# PressureSensorAdaptor.net
KiCad netlist of a schematic drawn in EAGLE
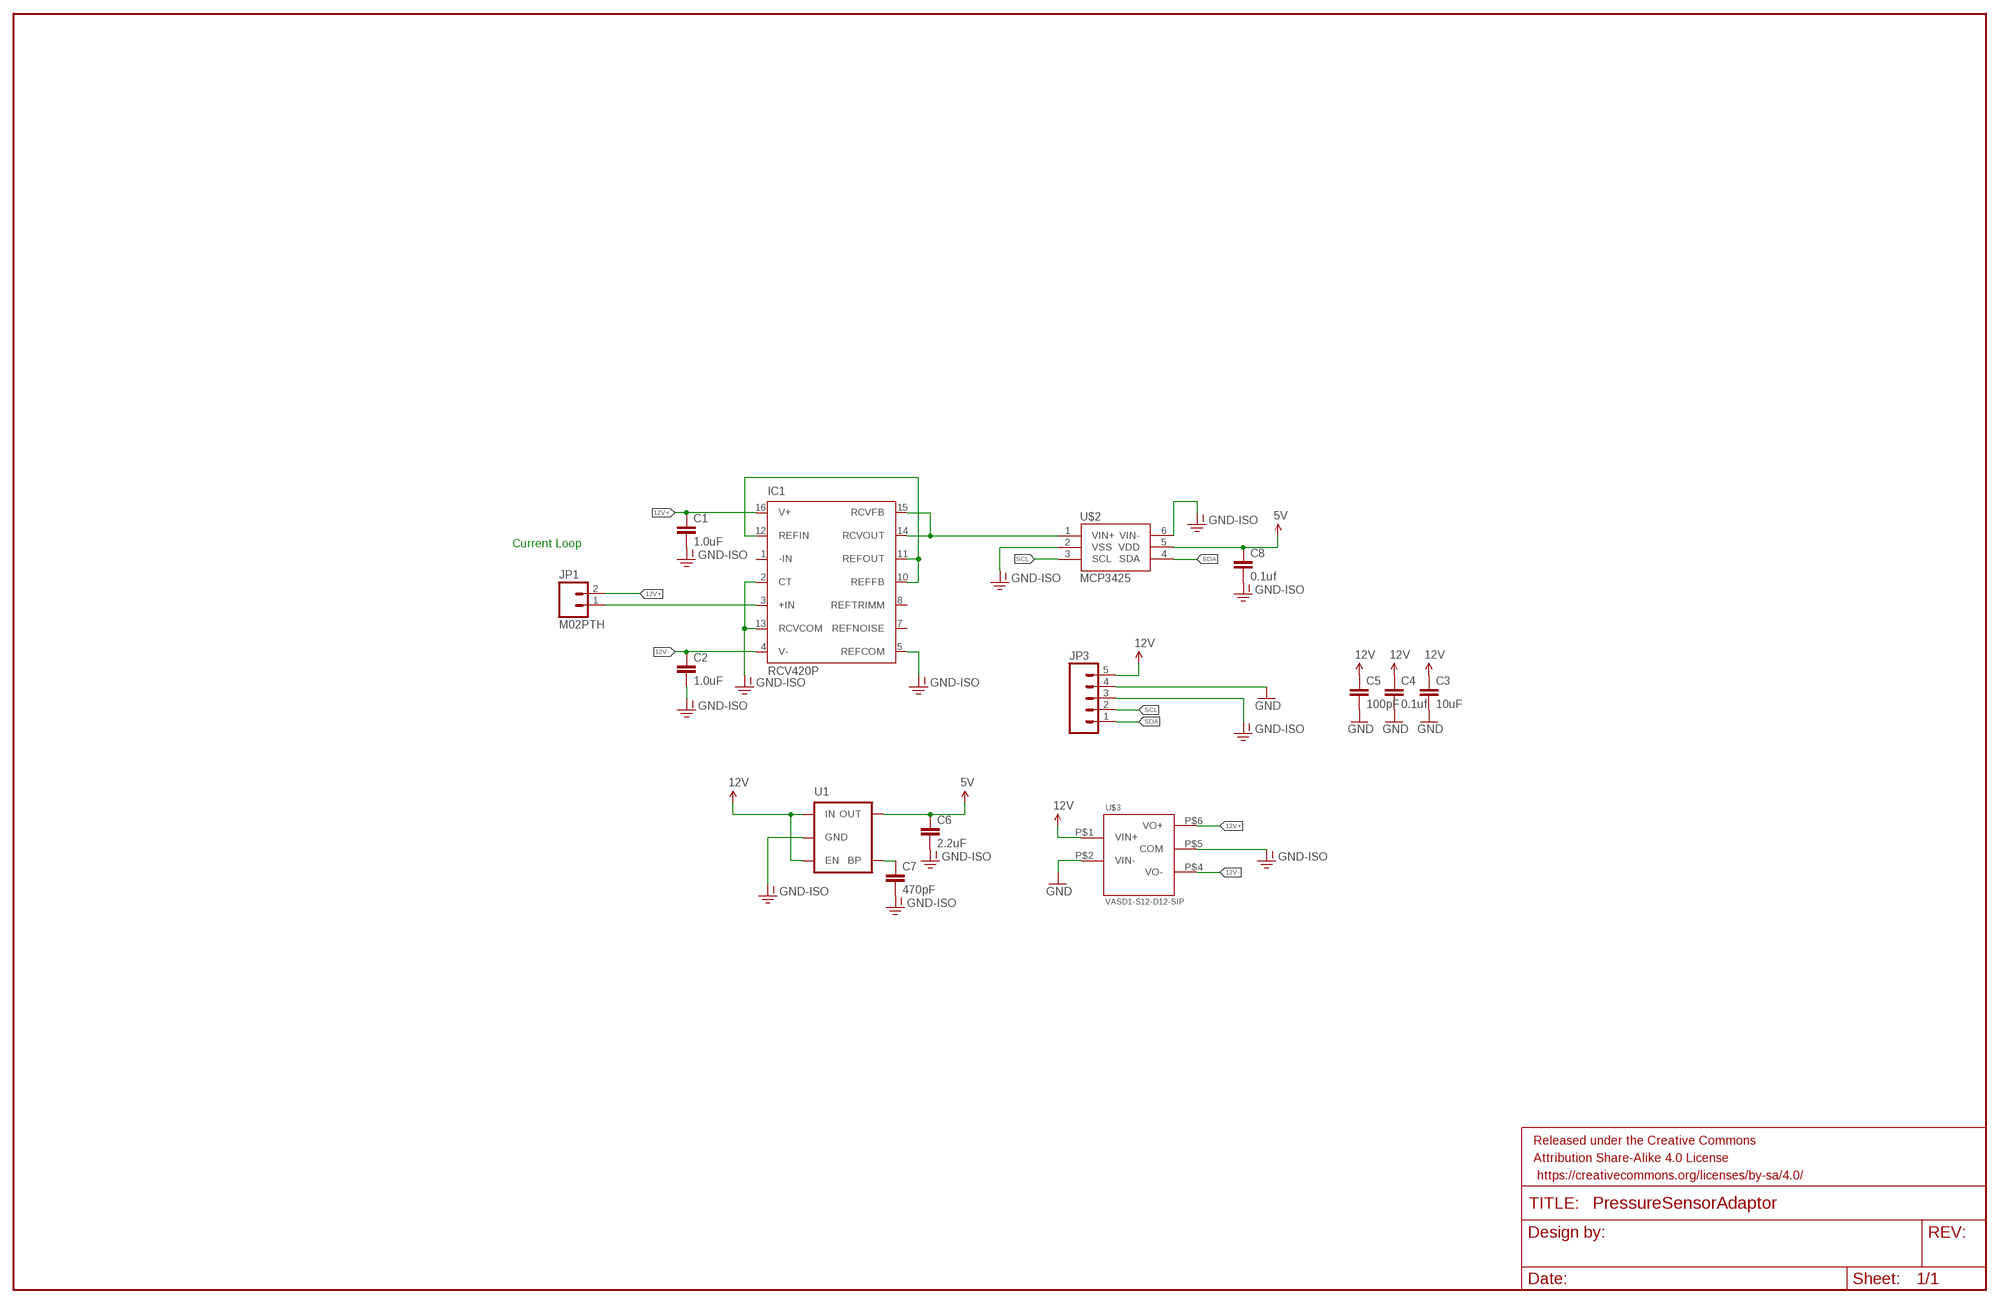
[diagram p0: schematic, sheet 1]

(export (version "E")
  (design (tool "Eeschema 10.0.6"))
  (components
    (comp (ref "C1")
      (value "1.0uF")
      (footprint "eagle-import:0805")
      (libsource (lib "eagle-import") (part "1.0UF-25V-+80/-20(0805)"))
    )
    (comp (ref "C2")
      (value "1.0uF")
      (footprint "eagle-import:0805")
      (libsource (lib "eagle-import") (part "1.0UF-25V-+80/-20(0805)"))
    )
    (comp (ref "C3")
      (value "10uF")
      (footprint "eagle-import:0805")
      (libsource (lib "eagle-import") (part "CAP0805"))
    )
    (comp (ref "C4")
      (value "0.1uf")
      (footprint "eagle-import:0805")
      (libsource (lib "eagle-import") (part "CAP0805"))
    )
    (comp (ref "C5")
      (value "100pF")
      (footprint "eagle-import:0805")
      (libsource (lib "eagle-import") (part "CAP0805"))
    )
    (comp (ref "C6")
      (value "2.2uF")
      (footprint "eagle-import:0805")
      (libsource (lib "eagle-import") (part "2.2UF-25V-+80/-20(0805)"))
    )
    (comp (ref "C7")
      (value "470pF")
      (footprint "eagle-import:0603-CAP")
      (libsource (lib "eagle-import") (part "470PF-50V-5%(0603)SMD"))
    )
    (comp (ref "C8")
      (value "0.1uf")
      (footprint "eagle-import:0805")
      (libsource (lib "eagle-import") (part "CAP0805"))
    )
    (comp (ref "FRAME1")
      (value "FRAME-LEDGER")
      (footprint "eagle-import:CREATIVE_COMMONS")
      (fields (field (name "DESIGNER") "Roy Cohen") (field (name "VERSION") "A"))
      (libsource (lib "eagle-import") (part "FRAME-LEDGER"))
    )
    (comp (ref "IC1")
      (value "RCV420P")
      (footprint "eagle-import:DIL16")
      (fields (field (name "MF") "TEXAS INSTRUMENTS") (field (name "MPN") "RCV420JP"))
      (libsource (lib "eagle-import") (part "RCV420P"))
    )
    (comp (ref "JP1")
      (value "M02PTH")
      (footprint "eagle-import:1X02")
      (libsource (lib "eagle-import") (part "M02PTH"))
    )
    (comp (ref "JP3")
      (value "M05PTH")
      (footprint "eagle-import:1X05")
      (libsource (lib "eagle-import") (part "M05PTH"))
    )
    (comp (ref "U$2")
      (value "MCP3425")
      (footprint "eagle-import:SOT23-6")
      (libsource (lib "eagle-import") (part "MCP3425"))
    )
    (comp (ref "U$3")
      (value "VASD1-S12-D12-SIP")
      (footprint "eagle-import:VASD1-S12-D12-SIP")
      (libsource (lib "eagle-import") (part "VASD1-S12-D12-SIP"))
    )
    (comp (ref "U1")
      (value "MIC52055V")
      (footprint "eagle-import:SOT23-5")
      (libsource (lib "eagle-import") (part "MIC52055V"))
    )
  )
  (nets
    (net (code "1") (name "5V") (class "Default")
      (node (ref "C6") (pin "1") (pinfunction "1_1") (pintype "passive"))
      (node (ref "C8") (pin "1") (pinfunction "1_1") (pintype "passive"))
      (node (ref "U$2") (pin "5") (pinfunction "VDD_5") (pintype "bidirectional"))
      (node (ref "U1") (pin "5") (pinfunction "OUT_5") (pintype "passive"))
    )
    (net (code "2") (name "12V") (class "Default")
      (node (ref "C3") (pin "1") (pinfunction "1_1") (pintype "passive"))
      (node (ref "C4") (pin "1") (pinfunction "1_1") (pintype "passive"))
      (node (ref "C5") (pin "1") (pinfunction "1_1") (pintype "passive"))
      (node (ref "JP3") (pin "5") (pinfunction "5_5") (pintype "passive"))
      (node (ref "U$3") (pin "P$1") (pinfunction "VIN+_P$1") (pintype "bidirectional"))
      (node (ref "U1") (pin "1") (pinfunction "IN_1") (pintype "input"))
      (node (ref "U1") (pin "3") (pinfunction "EN_3") (pintype "input"))
    )
    (net (code "3") (name "12V+") (class "Default")
      (node (ref "C1") (pin "1") (pinfunction "1_1") (pintype "passive"))
      (node (ref "IC1") (pin "16") (pinfunction "V+_16") (pintype "input"))
      (node (ref "JP1") (pin "2") (pinfunction "2_2") (pintype "passive"))
      (node (ref "U$3") (pin "P$6") (pinfunction "VO+_P$6") (pintype "bidirectional"))
    )
    (net (code "4") (name "12V-") (class "Default")
      (node (ref "C2") (pin "1") (pinfunction "1_1") (pintype "passive"))
      (node (ref "IC1") (pin "4") (pinfunction "V-_4") (pintype "input"))
      (node (ref "U$3") (pin "P$4") (pinfunction "VO-_P$4") (pintype "bidirectional"))
    )
    (net (code "5") (name "GND") (class "Default")
      (node (ref "C3") (pin "2") (pinfunction "2_2") (pintype "passive"))
      (node (ref "C4") (pin "2") (pinfunction "2_2") (pintype "passive"))
      (node (ref "C5") (pin "2") (pinfunction "2_2") (pintype "passive"))
      (node (ref "JP3") (pin "4") (pinfunction "4_4") (pintype "passive"))
      (node (ref "U$3") (pin "P$2") (pinfunction "VIN-_P$2") (pintype "bidirectional"))
    )
    (net (code "6") (name "GND-ISO") (class "Default")
      (node (ref "C1") (pin "2") (pinfunction "2_2") (pintype "passive"))
      (node (ref "C2") (pin "2") (pinfunction "2_2") (pintype "passive"))
      (node (ref "C6") (pin "2") (pinfunction "2_2") (pintype "passive"))
      (node (ref "C7") (pin "2") (pinfunction "2_2") (pintype "passive"))
      (node (ref "C8") (pin "2") (pinfunction "2_2") (pintype "passive"))
      (node (ref "IC1") (pin "13") (pinfunction "RCVCOM_13") (pintype "input"))
      (node (ref "IC1") (pin "2") (pinfunction "CT_2") (pintype "input"))
      (node (ref "IC1") (pin "5") (pinfunction "REFCOM_5") (pintype "input"))
      (node (ref "JP3") (pin "3") (pinfunction "3_3") (pintype "passive"))
      (node (ref "U$2") (pin "2") (pinfunction "VSS_2") (pintype "bidirectional"))
      (node (ref "U$2") (pin "6") (pinfunction "VIN-_6") (pintype "bidirectional"))
      (node (ref "U$3") (pin "P$5") (pinfunction "COM_P$5") (pintype "bidirectional"))
      (node (ref "U1") (pin "2") (pinfunction "GND_2") (pintype "input"))
    )
    (net (code "7") (name "Net-(IC1-+IN)") (class "Default")
      (node (ref "IC1") (pin "3") (pinfunction "+IN_3") (pintype "input"))
      (node (ref "JP1") (pin "1") (pinfunction "1_1") (pintype "passive"))
    )
    (net (code "8") (name "Net-(IC1-RCVFB)") (class "Default")
      (node (ref "IC1") (pin "14") (pinfunction "RCVOUT_14") (pintype "output"))
      (node (ref "IC1") (pin "15") (pinfunction "RCVFB_15") (pintype "input"))
      (node (ref "U$2") (pin "1") (pinfunction "VIN+_1") (pintype "bidirectional"))
    )
    (net (code "9") (name "Net-(IC1-REFFB)") (class "Default")
      (node (ref "IC1") (pin "10") (pinfunction "REFFB_10") (pintype "input"))
      (node (ref "IC1") (pin "11") (pinfunction "REFOUT_11") (pintype "output"))
      (node (ref "IC1") (pin "12") (pinfunction "REFIN_12") (pintype "input"))
    )
    (net (code "10") (name "Net-(U1-BP)") (class "Default")
      (node (ref "C7") (pin "1") (pinfunction "1_1") (pintype "passive"))
      (node (ref "U1") (pin "4") (pinfunction "BP_4") (pintype "input"))
    )
    (net (code "11") (name "SCL") (class "Default")
      (node (ref "JP3") (pin "2") (pinfunction "2_2") (pintype "passive"))
      (node (ref "U$2") (pin "3") (pinfunction "SCL_3") (pintype "bidirectional"))
    )
    (net (code "12") (name "SDA") (class "Default")
      (node (ref "JP3") (pin "1") (pinfunction "1_1") (pintype "passive"))
      (node (ref "U$2") (pin "4") (pinfunction "SDA_4") (pintype "bidirectional"))
    )
    (net (code "13") (name "unconnected-(IC1--IN-Pad1)") (class "Default")
      (node (ref "IC1") (pin "1") (pinfunction "-IN_1") (pintype "input"))
    )
    (net (code "14") (name "unconnected-(IC1-REFNOISE-Pad7)") (class "Default")
      (node (ref "IC1") (pin "7") (pinfunction "REFNOISE_7") (pintype "input"))
    )
    (net (code "15") (name "unconnected-(IC1-REFTRIMM-Pad8)") (class "Default")
      (node (ref "IC1") (pin "8") (pinfunction "REFTRIMM_8") (pintype "input"))
    )
  )
)
